# PARAMETRIK2L.net
KiCad netlist of a schematic drawn in EAGLE
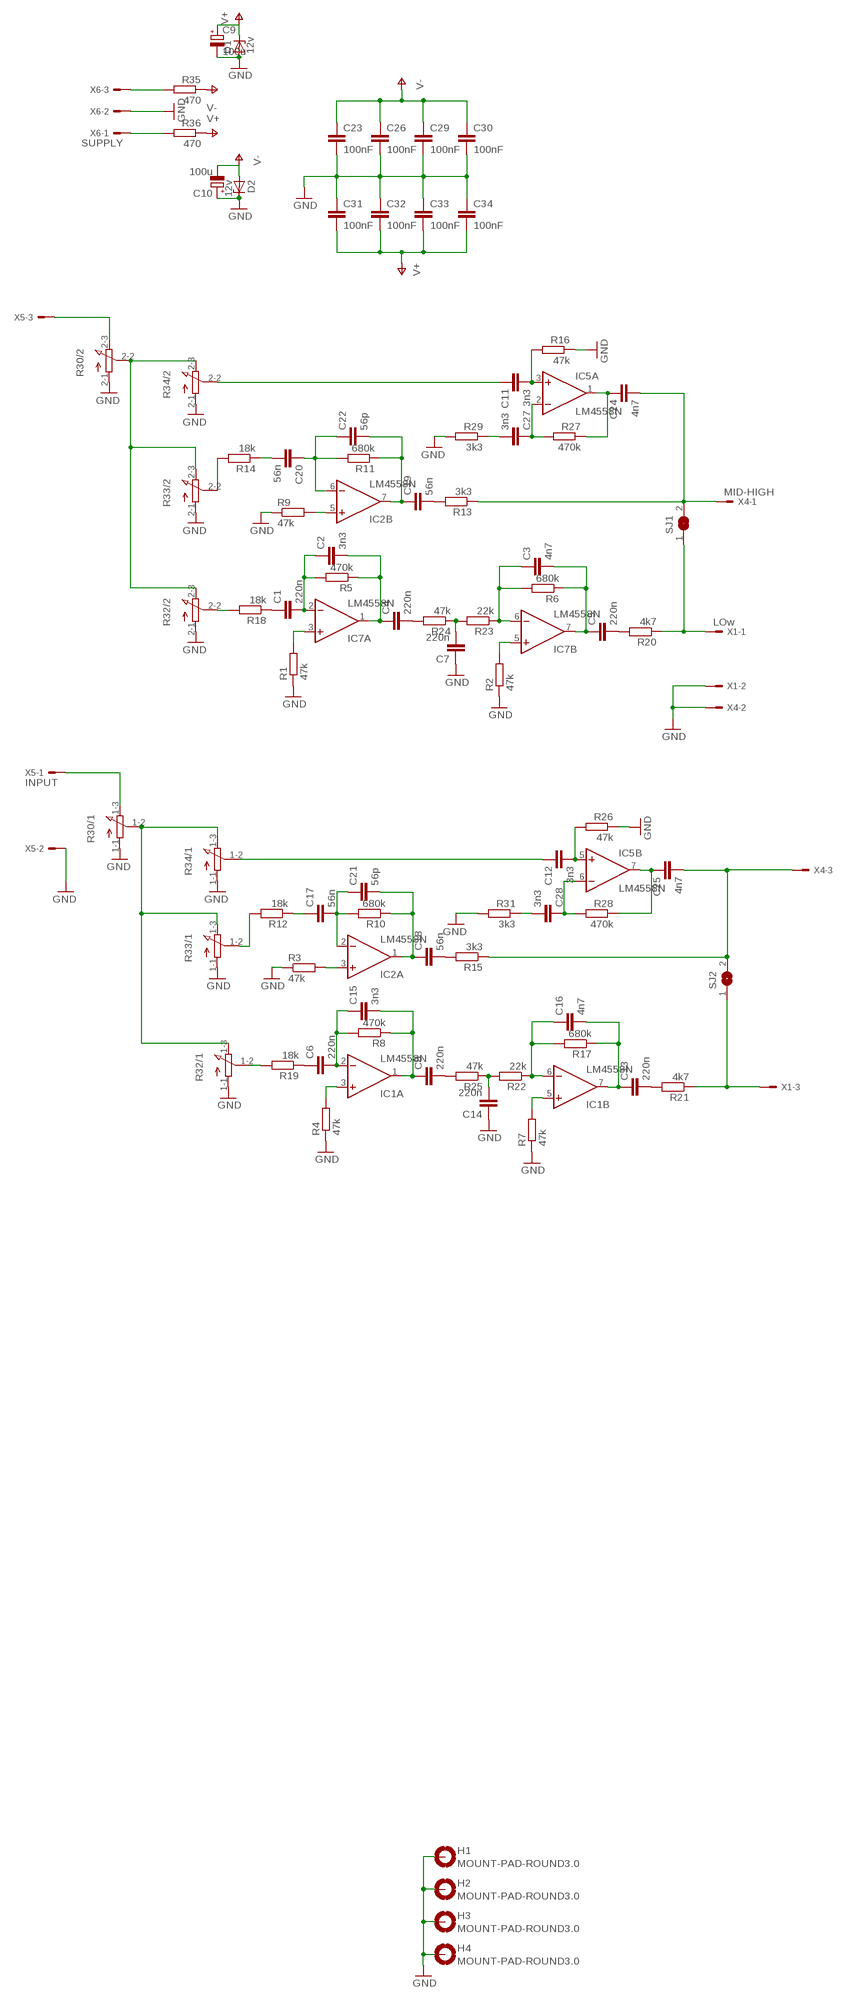
[diagram p0: schematic, sheet 1]

(export (version "E")
  (design (tool "Eeschema 10.0.6"))
  (components
    (comp (ref "C1")
      (value "220n")
      (footprint "eagle-import:C050-030X075")
      (libsource (lib "eagle-import") (part "C-EU050-030X075"))
    )
    (comp (ref "C2")
      (value "3n3")
      (footprint "eagle-import:C025-024X044")
      (libsource (lib "eagle-import") (part "C-EU025-024X044"))
    )
    (comp (ref "C3")
      (value "4n7")
      (footprint "eagle-import:C025-024X044")
      (libsource (lib "eagle-import") (part "C-EU025-024X044"))
    )
    (comp (ref "C4")
      (value "220n")
      (footprint "eagle-import:C050-030X075")
      (libsource (lib "eagle-import") (part "C-EU050-030X075"))
    )
    (comp (ref "C5")
      (value "220n")
      (footprint "eagle-import:C050-030X075")
      (libsource (lib "eagle-import") (part "C-EU050-030X075"))
    )
    (comp (ref "C6")
      (value "220n")
      (footprint "eagle-import:C050-030X075")
      (libsource (lib "eagle-import") (part "C-EU050-030X075"))
    )
    (comp (ref "C7")
      (value "220n")
      (footprint "eagle-import:C050-030X075")
      (libsource (lib "eagle-import") (part "C-EU050-030X075"))
    )
    (comp (ref "C8")
      (value "220n")
      (footprint "eagle-import:C050-030X075")
      (libsource (lib "eagle-import") (part "C-EU050-030X075"))
    )
    (comp (ref "C9")
      (value "100u")
      (footprint "eagle-import:E2,5-6")
      (libsource (lib "eagle-import") (part "CPOL-EUE2.5-6"))
    )
    (comp (ref "C10")
      (value "100u")
      (footprint "eagle-import:E2,5-6")
      (libsource (lib "eagle-import") (part "CPOL-EUE2.5-6"))
    )
    (comp (ref "C11")
      (value "3n3")
      (footprint "eagle-import:C025-024X044")
      (libsource (lib "eagle-import") (part "C-EU025-024X044"))
    )
    (comp (ref "C12")
      (value "3n3")
      (footprint "eagle-import:C025-024X044")
      (libsource (lib "eagle-import") (part "C-EU025-024X044"))
    )
    (comp (ref "C13")
      (value "220n")
      (footprint "eagle-import:C050-030X075")
      (libsource (lib "eagle-import") (part "C-EU050-030X075"))
    )
    (comp (ref "C14")
      (value "220n")
      (footprint "eagle-import:C050-030X075")
      (libsource (lib "eagle-import") (part "C-EU050-030X075"))
    )
    (comp (ref "C15")
      (value "3n3")
      (footprint "eagle-import:C025-024X044")
      (libsource (lib "eagle-import") (part "C-EU025-024X044"))
    )
    (comp (ref "C16")
      (value "4n7")
      (footprint "eagle-import:C025-024X044")
      (libsource (lib "eagle-import") (part "C-EU025-024X044"))
    )
    (comp (ref "C17")
      (value "56n")
      (footprint "eagle-import:C050-030X075")
      (libsource (lib "eagle-import") (part "C-EU050-030X075"))
    )
    (comp (ref "C18")
      (value "56n")
      (footprint "eagle-import:C050-030X075")
      (libsource (lib "eagle-import") (part "C-EU050-030X075"))
    )
    (comp (ref "C19")
      (value "56n")
      (footprint "eagle-import:C050-030X075")
      (libsource (lib "eagle-import") (part "C-EU050-030X075"))
    )
    (comp (ref "C20")
      (value "56n")
      (footprint "eagle-import:C050-030X075")
      (libsource (lib "eagle-import") (part "C-EU050-030X075"))
    )
    (comp (ref "C21")
      (value "56p")
      (footprint "eagle-import:C025-024X044")
      (libsource (lib "eagle-import") (part "C-EU025-024X044"))
    )
    (comp (ref "C22")
      (value "56p")
      (footprint "eagle-import:C025-024X044")
      (libsource (lib "eagle-import") (part "C-EU025-024X044"))
    )
    (comp (ref "C23")
      (value "100nF")
      (footprint "eagle-import:C050-024X044")
      (libsource (lib "eagle-import") (part "C-EU050-024X044"))
    )
    (comp (ref "C24")
      (value "4n7")
      (footprint "eagle-import:C025-024X044")
      (libsource (lib "eagle-import") (part "C-EU025-024X044"))
    )
    (comp (ref "C25")
      (value "4n7")
      (footprint "eagle-import:C025-024X044")
      (libsource (lib "eagle-import") (part "C-EU025-024X044"))
    )
    (comp (ref "C26")
      (value "100nF")
      (footprint "eagle-import:C050-024X044")
      (libsource (lib "eagle-import") (part "C-EU050-024X044"))
    )
    (comp (ref "C27")
      (value "3n3")
      (footprint "eagle-import:C025-024X044")
      (libsource (lib "eagle-import") (part "C-EU025-024X044"))
    )
    (comp (ref "C28")
      (value "3n3")
      (footprint "eagle-import:C025-024X044")
      (libsource (lib "eagle-import") (part "C-EU025-024X044"))
    )
    (comp (ref "C29")
      (value "100nF")
      (footprint "eagle-import:C050-024X044")
      (libsource (lib "eagle-import") (part "C-EU050-024X044"))
    )
    (comp (ref "C30")
      (value "100nF")
      (footprint "eagle-import:C050-024X044")
      (libsource (lib "eagle-import") (part "C-EU050-024X044"))
    )
    (comp (ref "C31")
      (value "100nF")
      (footprint "eagle-import:C050-024X044")
      (libsource (lib "eagle-import") (part "C-EU050-024X044"))
    )
    (comp (ref "C32")
      (value "100nF")
      (footprint "eagle-import:C050-024X044")
      (libsource (lib "eagle-import") (part "C-EU050-024X044"))
    )
    (comp (ref "C33")
      (value "100nF")
      (footprint "eagle-import:C050-024X044")
      (libsource (lib "eagle-import") (part "C-EU050-024X044"))
    )
    (comp (ref "C34")
      (value "100nF")
      (footprint "eagle-import:C050-024X044")
      (libsource (lib "eagle-import") (part "C-EU050-024X044"))
    )
    (comp (ref "D1")
      (value "12v")
      (footprint "eagle-import:DO35Z10")
      (libsource (lib "eagle-import") (part "1N821"))
    )
    (comp (ref "D2")
      (value "12v")
      (footprint "eagle-import:DO35Z10")
      (libsource (lib "eagle-import") (part "1N821"))
    )
    (comp (ref "H1")
      (value "MOUNT-PAD-ROUND3.0")
      (footprint "eagle-import:3,0-PAD")
      (libsource (lib "eagle-import") (part "MOUNT-PAD-ROUND3.0"))
    )
    (comp (ref "H2")
      (value "MOUNT-PAD-ROUND3.0")
      (footprint "eagle-import:3,0-PAD")
      (libsource (lib "eagle-import") (part "MOUNT-PAD-ROUND3.0"))
    )
    (comp (ref "H3")
      (value "MOUNT-PAD-ROUND3.0")
      (footprint "eagle-import:3,0-PAD")
      (libsource (lib "eagle-import") (part "MOUNT-PAD-ROUND3.0"))
    )
    (comp (ref "H4")
      (value "MOUNT-PAD-ROUND3.0")
      (footprint "eagle-import:3,0-PAD")
      (libsource (lib "eagle-import") (part "MOUNT-PAD-ROUND3.0"))
    )
    (comp (ref "IC1")
      (value "LM4558N")
      (footprint "eagle-import:DIL08")
      (libsource (lib "eagle-import") (part "4558NLM"))
    )
    (comp (ref "IC2")
      (value "LM4558N")
      (footprint "eagle-import:DIL08")
      (libsource (lib "eagle-import") (part "4558NLM"))
    )
    (comp (ref "IC5")
      (value "LM4558N")
      (footprint "eagle-import:DIL08")
      (libsource (lib "eagle-import") (part "4558NLM"))
    )
    (comp (ref "IC7")
      (value "LM4558N")
      (footprint "eagle-import:DIL08")
      (libsource (lib "eagle-import") (part "4558NLM"))
    )
    (comp (ref "R1")
      (value "47k")
      (footprint "eagle-import:0207_2V")
      (libsource (lib "eagle-import") (part "R-EU_0207/2V"))
    )
    (comp (ref "R2")
      (value "47k")
      (footprint "eagle-import:0207_2V")
      (libsource (lib "eagle-import") (part "R-EU_0207/2V"))
    )
    (comp (ref "R3")
      (value "47k")
      (footprint "eagle-import:0207_2V")
      (libsource (lib "eagle-import") (part "R-EU_0207/2V"))
    )
    (comp (ref "R4")
      (value "47k")
      (footprint "eagle-import:0207_2V")
      (libsource (lib "eagle-import") (part "R-EU_0207/2V"))
    )
    (comp (ref "R5")
      (value "470k")
      (footprint "eagle-import:0207_2V")
      (libsource (lib "eagle-import") (part "R-EU_0207/2V"))
    )
    (comp (ref "R6")
      (value "680k")
      (footprint "eagle-import:0207_2V")
      (libsource (lib "eagle-import") (part "R-EU_0207/2V"))
    )
    (comp (ref "R7")
      (value "47k")
      (footprint "eagle-import:0207_2V")
      (libsource (lib "eagle-import") (part "R-EU_0207/2V"))
    )
    (comp (ref "R8")
      (value "470k")
      (footprint "eagle-import:0207_2V")
      (libsource (lib "eagle-import") (part "R-EU_0207/2V"))
    )
    (comp (ref "R9")
      (value "47k")
      (footprint "eagle-import:0207_2V")
      (libsource (lib "eagle-import") (part "R-EU_0207/2V"))
    )
    (comp (ref "R10")
      (value "680k")
      (footprint "eagle-import:0207_2V")
      (libsource (lib "eagle-import") (part "R-EU_0207/2V"))
    )
    (comp (ref "R11")
      (value "680k")
      (footprint "eagle-import:0207_2V")
      (libsource (lib "eagle-import") (part "R-EU_0207/2V"))
    )
    (comp (ref "R12")
      (value "18k")
      (footprint "eagle-import:0207_2V")
      (libsource (lib "eagle-import") (part "R-EU_0207/2V"))
    )
    (comp (ref "R13")
      (value "3k3")
      (footprint "eagle-import:0207_2V")
      (libsource (lib "eagle-import") (part "R-EU_0207/2V"))
    )
    (comp (ref "R14")
      (value "18k")
      (footprint "eagle-import:0207_2V")
      (libsource (lib "eagle-import") (part "R-EU_0207/2V"))
    )
    (comp (ref "R15")
      (value "3k3")
      (footprint "eagle-import:0207_2V")
      (libsource (lib "eagle-import") (part "R-EU_0207/2V"))
    )
    (comp (ref "R16")
      (value "47k")
      (footprint "eagle-import:0207_2V")
      (libsource (lib "eagle-import") (part "R-EU_0207/2V"))
    )
    (comp (ref "R17")
      (value "680k")
      (footprint "eagle-import:0207_2V")
      (libsource (lib "eagle-import") (part "R-EU_0207/2V"))
    )
    (comp (ref "R18")
      (value "18k")
      (footprint "eagle-import:0207_2V")
      (libsource (lib "eagle-import") (part "R-EU_0207/2V"))
    )
    (comp (ref "R19")
      (value "18k")
      (footprint "eagle-import:0207_2V")
      (libsource (lib "eagle-import") (part "R-EU_0207/2V"))
    )
    (comp (ref "R20")
      (value "4k7")
      (footprint "eagle-import:0207_2V")
      (libsource (lib "eagle-import") (part "R-EU_0207/2V"))
    )
    (comp (ref "R21")
      (value "4k7")
      (footprint "eagle-import:0207_2V")
      (libsource (lib "eagle-import") (part "R-EU_0207/2V"))
    )
    (comp (ref "R22")
      (value "22k")
      (footprint "eagle-import:0207_2V")
      (libsource (lib "eagle-import") (part "R-EU_0207/2V"))
    )
    (comp (ref "R23")
      (value "22k")
      (footprint "eagle-import:0207_2V")
      (libsource (lib "eagle-import") (part "R-EU_0207/2V"))
    )
    (comp (ref "R24")
      (value "47k")
      (footprint "eagle-import:0207_2V")
      (libsource (lib "eagle-import") (part "R-EU_0207/2V"))
    )
    (comp (ref "R25")
      (value "47k")
      (footprint "eagle-import:0207_2V")
      (libsource (lib "eagle-import") (part "R-EU_0207/2V"))
    )
    (comp (ref "R26")
      (value "47k")
      (footprint "eagle-import:0207_2V")
      (libsource (lib "eagle-import") (part "R-EU_0207/2V"))
    )
    (comp (ref "R27")
      (value "470k")
      (footprint "eagle-import:0207_2V")
      (libsource (lib "eagle-import") (part "R-EU_0207/2V"))
    )
    (comp (ref "R28")
      (value "470k")
      (footprint "eagle-import:0207_2V")
      (libsource (lib "eagle-import") (part "R-EU_0207/2V"))
    )
    (comp (ref "R29")
      (value "3k3")
      (footprint "eagle-import:0207_2V")
      (libsource (lib "eagle-import") (part "R-EU_0207/2V"))
    )
    (comp (ref "R30")
      (value "3RP/1610G")
      (footprint "eagle-import:3RP_1610G")
      (libsource (lib "eagle-import") (part "3RP/1610G"))
    )
    (comp (ref "R31")
      (value "3k3")
      (footprint "eagle-import:0207_2V")
      (libsource (lib "eagle-import") (part "R-EU_0207/2V"))
    )
    (comp (ref "R32")
      (value "3RP/1610G")
      (footprint "eagle-import:3RP_1610G")
      (libsource (lib "eagle-import") (part "3RP/1610G"))
    )
    (comp (ref "R33")
      (value "3RP/1610G")
      (footprint "eagle-import:3RP_1610G")
      (libsource (lib "eagle-import") (part "3RP/1610G"))
    )
    (comp (ref "R34")
      (value "3RP/1610G")
      (footprint "eagle-import:3RP_1610G")
      (libsource (lib "eagle-import") (part "3RP/1610G"))
    )
    (comp (ref "R35")
      (value "470")
      (footprint "eagle-import:0207_10")
      (libsource (lib "eagle-import") (part "R-EU_0207/10"))
    )
    (comp (ref "R36")
      (value "470")
      (footprint "eagle-import:0207_10")
      (libsource (lib "eagle-import") (part "R-EU_0207/10"))
    )
    (comp (ref "SJ1") (value "SJ") (footprint "eagle-import:SJ") (libsource (lib "eagle-import") (part "SJ")))
    (comp (ref "SJ2") (value "SJ") (footprint "eagle-import:SJ") (libsource (lib "eagle-import") (part "SJ")))
    (comp (ref "X1")
      (value "LOw")
      (footprint "eagle-import:22-23-2031")
      (fields (field (name "MF") "MOLEX") (field (name "MPN") "22-23-2031"))
      (libsource (lib "eagle-import") (part "22-23-2031"))
    )
    (comp (ref "X4")
      (value "MID-HIGH")
      (footprint "eagle-import:22-23-2031")
      (fields (field (name "MF") "MOLEX") (field (name "MPN") "22-23-2031"))
      (libsource (lib "eagle-import") (part "22-23-2031"))
    )
    (comp (ref "X5")
      (value "INPUT")
      (footprint "eagle-import:22-23-2031")
      (fields (field (name "MF") "MOLEX") (field (name "MPN") "22-23-2031"))
      (libsource (lib "eagle-import") (part "22-23-2031"))
    )
    (comp (ref "X6")
      (value "SUPPLY")
      (footprint "eagle-import:22-23-2031")
      (fields (field (name "MF") "MOLEX") (field (name "MPN") "22-23-2031"))
      (libsource (lib "eagle-import") (part "22-23-2031"))
    )
  )
  (nets
    (net (code "1") (name "GND") (class "Default")
      (node (ref "C10") (pin "+") (pinfunction "+_+") (pintype "passive"))
      (node (ref "C14") (pin "1") (pinfunction "1_1") (pintype "passive"))
      (node (ref "C23") (pin "2") (pinfunction "2_2") (pintype "passive"))
      (node (ref "C26") (pin "2") (pinfunction "2_2") (pintype "passive"))
      (node (ref "C29") (pin "2") (pinfunction "2_2") (pintype "passive"))
      (node (ref "C30") (pin "2") (pinfunction "2_2") (pintype "passive"))
      (node (ref "C31") (pin "1") (pinfunction "1_1") (pintype "passive"))
      (node (ref "C32") (pin "1") (pinfunction "1_1") (pintype "passive"))
      (node (ref "C33") (pin "1") (pinfunction "1_1") (pintype "passive"))
      (node (ref "C34") (pin "1") (pinfunction "1_1") (pintype "passive"))
      (node (ref "C7") (pin "1") (pinfunction "1_1") (pintype "passive"))
      (node (ref "C9") (pin "-") (pinfunction "-_-") (pintype "passive"))
      (node (ref "D1") (pin "A") (pinfunction "A_A") (pintype "passive"))
      (node (ref "D2") (pin "C") (pinfunction "C_C") (pintype "passive"))
      (node (ref "H1") (pin "B3,0") (pinfunction "MOUNT_B3,0") (pintype "passive"))
      (node (ref "H2") (pin "B3,0") (pinfunction "MOUNT_B3,0") (pintype "passive"))
      (node (ref "H3") (pin "B3,0") (pinfunction "MOUNT_B3,0") (pintype "passive"))
      (node (ref "H4") (pin "B3,0") (pinfunction "MOUNT_B3,0") (pintype "passive"))
      (node (ref "R1") (pin "1") (pinfunction "1_1") (pintype "passive"))
      (node (ref "R16") (pin "1") (pinfunction "1_1") (pintype "passive"))
      (node (ref "R2") (pin "1") (pinfunction "1_1") (pintype "passive"))
      (node (ref "R26") (pin "1") (pinfunction "1_1") (pintype "passive"))
      (node (ref "R29") (pin "2") (pinfunction "2_2") (pintype "passive"))
      (node (ref "R3") (pin "1") (pinfunction "1_1") (pintype "passive"))
      (node (ref "R30") (pin "1-1") (pinfunction "A_1-1") (pintype "passive"))
      (node (ref "R30") (pin "2-1") (pinfunction "A_2-1") (pintype "passive"))
      (node (ref "R31") (pin "2") (pinfunction "2_2") (pintype "passive"))
      (node (ref "R32") (pin "1-1") (pinfunction "A_1-1") (pintype "passive"))
      (node (ref "R32") (pin "2-1") (pinfunction "A_2-1") (pintype "passive"))
      (node (ref "R33") (pin "1-1") (pinfunction "A_1-1") (pintype "passive"))
      (node (ref "R33") (pin "2-1") (pinfunction "A_2-1") (pintype "passive"))
      (node (ref "R34") (pin "1-1") (pinfunction "A_1-1") (pintype "passive"))
      (node (ref "R34") (pin "2-1") (pinfunction "A_2-1") (pintype "passive"))
      (node (ref "R4") (pin "1") (pinfunction "1_1") (pintype "passive"))
      (node (ref "R7") (pin "1") (pinfunction "1_1") (pintype "passive"))
      (node (ref "R9") (pin "1") (pinfunction "1_1") (pintype "passive"))
      (node (ref "X1") (pin "2") (pinfunction "S_2") (pintype "passive"))
      (node (ref "X4") (pin "2") (pinfunction "S_2") (pintype "passive"))
      (node (ref "X5") (pin "2") (pinfunction "S_2") (pintype "passive"))
      (node (ref "X6") (pin "2") (pinfunction "S_2") (pintype "passive"))
    )
    (net (code "2") (name "Net-(C1-Pad1)") (class "Default")
      (node (ref "C1") (pin "1") (pinfunction "1_1") (pintype "passive"))
      (node (ref "R18") (pin "1") (pinfunction "1_1") (pintype "passive"))
    )
    (net (code "3") (name "Net-(C4-Pad2)") (class "Default")
      (node (ref "C4") (pin "2") (pinfunction "2_2") (pintype "passive"))
      (node (ref "R24") (pin "2") (pinfunction "2_2") (pintype "passive"))
    )
    (net (code "4") (name "Net-(C5-Pad2)") (class "Default")
      (node (ref "C5") (pin "2") (pinfunction "2_2") (pintype "passive"))
      (node (ref "R20") (pin "2") (pinfunction "2_2") (pintype "passive"))
    )
    (net (code "5") (name "Net-(C6-Pad1)") (class "Default")
      (node (ref "C6") (pin "1") (pinfunction "1_1") (pintype "passive"))
      (node (ref "R19") (pin "1") (pinfunction "1_1") (pintype "passive"))
    )
    (net (code "6") (name "Net-(C7-Pad2)") (class "Default")
      (node (ref "C7") (pin "2") (pinfunction "2_2") (pintype "passive"))
      (node (ref "R23") (pin "2") (pinfunction "2_2") (pintype "passive"))
      (node (ref "R24") (pin "1") (pinfunction "1_1") (pintype "passive"))
    )
    (net (code "7") (name "Net-(C8-Pad2)") (class "Default")
      (node (ref "C8") (pin "2") (pinfunction "2_2") (pintype "passive"))
      (node (ref "R25") (pin "2") (pinfunction "2_2") (pintype "passive"))
    )
    (net (code "8") (name "Net-(C13-Pad2)") (class "Default")
      (node (ref "C13") (pin "2") (pinfunction "2_2") (pintype "passive"))
      (node (ref "R21") (pin "2") (pinfunction "2_2") (pintype "passive"))
    )
    (net (code "9") (name "Net-(C14-Pad2)") (class "Default")
      (node (ref "C14") (pin "2") (pinfunction "2_2") (pintype "passive"))
      (node (ref "R22") (pin "2") (pinfunction "2_2") (pintype "passive"))
      (node (ref "R25") (pin "1") (pinfunction "1_1") (pintype "passive"))
    )
    (net (code "10") (name "Net-(C17-Pad1)") (class "Default")
      (node (ref "C17") (pin "1") (pinfunction "1_1") (pintype "passive"))
      (node (ref "R12") (pin "1") (pinfunction "1_1") (pintype "passive"))
    )
    (net (code "11") (name "Net-(C18-Pad2)") (class "Default")
      (node (ref "C18") (pin "2") (pinfunction "2_2") (pintype "passive"))
      (node (ref "R15") (pin "2") (pinfunction "2_2") (pintype "passive"))
    )
    (net (code "12") (name "Net-(C19-Pad2)") (class "Default")
      (node (ref "C19") (pin "2") (pinfunction "2_2") (pintype "passive"))
      (node (ref "R13") (pin "2") (pinfunction "2_2") (pintype "passive"))
    )
    (net (code "13") (name "Net-(C20-Pad2)") (class "Default")
      (node (ref "C20") (pin "2") (pinfunction "2_2") (pintype "passive"))
      (node (ref "R14") (pin "1") (pinfunction "1_1") (pintype "passive"))
    )
    (net (code "14") (name "Net-(C27-Pad2)") (class "Default")
      (node (ref "C27") (pin "2") (pinfunction "2_2") (pintype "passive"))
      (node (ref "R29") (pin "1") (pinfunction "1_1") (pintype "passive"))
    )
    (net (code "15") (name "Net-(C28-Pad2)") (class "Default")
      (node (ref "C28") (pin "2") (pinfunction "2_2") (pintype "passive"))
      (node (ref "R31") (pin "1") (pinfunction "1_1") (pintype "passive"))
    )
    (net (code "16") (name "Net-(IC1A-+IN)") (class "Default")
      (node (ref "IC1") (pin "3") (pinfunction "+IN_3") (pintype "input"))
      (node (ref "R4") (pin "2") (pinfunction "2_2") (pintype "passive"))
    )
    (net (code "17") (name "Net-(IC1A--IN)") (class "Default")
      (node (ref "C15") (pin "1") (pinfunction "1_1") (pintype "passive"))
      (node (ref "C6") (pin "2") (pinfunction "2_2") (pintype "passive"))
      (node (ref "IC1") (pin "2") (pinfunction "-IN_2") (pintype "input"))
      (node (ref "R8") (pin "2") (pinfunction "2_2") (pintype "passive"))
    )
    (net (code "18") (name "Net-(IC1A-OUT)") (class "Default")
      (node (ref "C15") (pin "2") (pinfunction "2_2") (pintype "passive"))
      (node (ref "C8") (pin "1") (pinfunction "1_1") (pintype "passive"))
      (node (ref "IC1") (pin "1") (pinfunction "OUT_1") (pintype "output"))
      (node (ref "R8") (pin "1") (pinfunction "1_1") (pintype "passive"))
    )
    (net (code "19") (name "Net-(IC1B-+IN)") (class "Default")
      (node (ref "IC1") (pin "5") (pinfunction "+IN_5") (pintype "input"))
      (node (ref "R7") (pin "2") (pinfunction "2_2") (pintype "passive"))
    )
    (net (code "20") (name "Net-(IC1B--IN)") (class "Default")
      (node (ref "C16") (pin "1") (pinfunction "1_1") (pintype "passive"))
      (node (ref "IC1") (pin "6") (pinfunction "-IN_6") (pintype "input"))
      (node (ref "R17") (pin "2") (pinfunction "2_2") (pintype "passive"))
      (node (ref "R22") (pin "1") (pinfunction "1_1") (pintype "passive"))
    )
    (net (code "21") (name "Net-(IC1B-OUT)") (class "Default")
      (node (ref "C13") (pin "1") (pinfunction "1_1") (pintype "passive"))
      (node (ref "C16") (pin "2") (pinfunction "2_2") (pintype "passive"))
      (node (ref "IC1") (pin "7") (pinfunction "OUT_7") (pintype "output"))
      (node (ref "R17") (pin "1") (pinfunction "1_1") (pintype "passive"))
    )
    (net (code "22") (name "Net-(IC2A-+IN)") (class "Default")
      (node (ref "IC2") (pin "3") (pinfunction "+IN_3") (pintype "input"))
      (node (ref "R3") (pin "2") (pinfunction "2_2") (pintype "passive"))
    )
    (net (code "23") (name "Net-(IC2A--IN)") (class "Default")
      (node (ref "C17") (pin "2") (pinfunction "2_2") (pintype "passive"))
      (node (ref "C21") (pin "1") (pinfunction "1_1") (pintype "passive"))
      (node (ref "IC2") (pin "2") (pinfunction "-IN_2") (pintype "input"))
      (node (ref "R10") (pin "2") (pinfunction "2_2") (pintype "passive"))
    )
    (net (code "24") (name "Net-(IC2A-OUT)") (class "Default")
      (node (ref "C18") (pin "1") (pinfunction "1_1") (pintype "passive"))
      (node (ref "C21") (pin "2") (pinfunction "2_2") (pintype "passive"))
      (node (ref "IC2") (pin "1") (pinfunction "OUT_1") (pintype "output"))
      (node (ref "R10") (pin "1") (pinfunction "1_1") (pintype "passive"))
    )
    (net (code "25") (name "Net-(IC2B-+IN)") (class "Default")
      (node (ref "IC2") (pin "5") (pinfunction "+IN_5") (pintype "input"))
      (node (ref "R9") (pin "2") (pinfunction "2_2") (pintype "passive"))
    )
    (net (code "26") (name "Net-(IC2B--IN)") (class "Default")
      (node (ref "C20") (pin "1") (pinfunction "1_1") (pintype "passive"))
      (node (ref "C22") (pin "1") (pinfunction "1_1") (pintype "passive"))
      (node (ref "IC2") (pin "6") (pinfunction "-IN_6") (pintype "input"))
      (node (ref "R11") (pin "2") (pinfunction "2_2") (pintype "passive"))
    )
    (net (code "27") (name "Net-(IC2B-OUT)") (class "Default")
      (node (ref "C19") (pin "1") (pinfunction "1_1") (pintype "passive"))
      (node (ref "C22") (pin "2") (pinfunction "2_2") (pintype "passive"))
      (node (ref "IC2") (pin "7") (pinfunction "OUT_7") (pintype "output"))
      (node (ref "R11") (pin "1") (pinfunction "1_1") (pintype "passive"))
    )
    (net (code "28") (name "Net-(IC5A-+IN)") (class "Default")
      (node (ref "C11") (pin "2") (pinfunction "2_2") (pintype "passive"))
      (node (ref "IC5") (pin "3") (pinfunction "+IN_3") (pintype "input"))
      (node (ref "R16") (pin "2") (pinfunction "2_2") (pintype "passive"))
    )
    (net (code "29") (name "Net-(IC5A--IN)") (class "Default")
      (node (ref "C27") (pin "1") (pinfunction "1_1") (pintype "passive"))
      (node (ref "IC5") (pin "2") (pinfunction "-IN_2") (pintype "input"))
      (node (ref "R27") (pin "2") (pinfunction "2_2") (pintype "passive"))
    )
    (net (code "30") (name "Net-(IC5A-OUT)") (class "Default")
      (node (ref "C24") (pin "1") (pinfunction "1_1") (pintype "passive"))
      (node (ref "IC5") (pin "1") (pinfunction "OUT_1") (pintype "output"))
      (node (ref "R27") (pin "1") (pinfunction "1_1") (pintype "passive"))
    )
    (net (code "31") (name "Net-(IC5B-+IN)") (class "Default")
      (node (ref "C12") (pin "2") (pinfunction "2_2") (pintype "passive"))
      (node (ref "IC5") (pin "5") (pinfunction "+IN_5") (pintype "input"))
      (node (ref "R26") (pin "2") (pinfunction "2_2") (pintype "passive"))
    )
    (net (code "32") (name "Net-(IC5B--IN)") (class "Default")
      (node (ref "C28") (pin "1") (pinfunction "1_1") (pintype "passive"))
      (node (ref "IC5") (pin "6") (pinfunction "-IN_6") (pintype "input"))
      (node (ref "R28") (pin "2") (pinfunction "2_2") (pintype "passive"))
    )
    (net (code "33") (name "Net-(IC5B-OUT)") (class "Default")
      (node (ref "C25") (pin "1") (pinfunction "1_1") (pintype "passive"))
      (node (ref "IC5") (pin "7") (pinfunction "OUT_7") (pintype "output"))
      (node (ref "R28") (pin "1") (pinfunction "1_1") (pintype "passive"))
    )
    (net (code "34") (name "Net-(IC7A-+IN)") (class "Default")
      (node (ref "IC7") (pin "3") (pinfunction "+IN_3") (pintype "input"))
      (node (ref "R1") (pin "2") (pinfunction "2_2") (pintype "passive"))
    )
    (net (code "35") (name "Net-(IC7A--IN)") (class "Default")
      (node (ref "C1") (pin "2") (pinfunction "2_2") (pintype "passive"))
      (node (ref "C2") (pin "1") (pinfunction "1_1") (pintype "passive"))
      (node (ref "IC7") (pin "2") (pinfunction "-IN_2") (pintype "input"))
      (node (ref "R5") (pin "2") (pinfunction "2_2") (pintype "passive"))
    )
    (net (code "36") (name "Net-(IC7A-OUT)") (class "Default")
      (node (ref "C2") (pin "2") (pinfunction "2_2") (pintype "passive"))
      (node (ref "C4") (pin "1") (pinfunction "1_1") (pintype "passive"))
      (node (ref "IC7") (pin "1") (pinfunction "OUT_1") (pintype "output"))
      (node (ref "R5") (pin "1") (pinfunction "1_1") (pintype "passive"))
    )
    (net (code "37") (name "Net-(IC7B-+IN)") (class "Default")
      (node (ref "IC7") (pin "5") (pinfunction "+IN_5") (pintype "input"))
      (node (ref "R2") (pin "2") (pinfunction "2_2") (pintype "passive"))
    )
    (net (code "38") (name "Net-(IC7B--IN)") (class "Default")
      (node (ref "C3") (pin "1") (pinfunction "1_1") (pintype "passive"))
      (node (ref "IC7") (pin "6") (pinfunction "-IN_6") (pintype "input"))
      (node (ref "R23") (pin "1") (pinfunction "1_1") (pintype "passive"))
      (node (ref "R6") (pin "2") (pinfunction "2_2") (pintype "passive"))
    )
    (net (code "39") (name "Net-(IC7B-OUT)") (class "Default")
      (node (ref "C3") (pin "2") (pinfunction "2_2") (pintype "passive"))
      (node (ref "C5") (pin "1") (pinfunction "1_1") (pintype "passive"))
      (node (ref "IC7") (pin "7") (pinfunction "OUT_7") (pintype "output"))
      (node (ref "R6") (pin "1") (pinfunction "1_1") (pintype "passive"))
    )
    (net (code "40") (name "Net-(R30A-E)") (class "Default")
      (node (ref "R30") (pin "1-3") (pinfunction "E_1-3") (pintype "passive"))
      (node (ref "X5") (pin "1") (pinfunction "S_1") (pintype "passive"))
    )
    (net (code "41") (name "Net-(R30A-S)") (class "Default")
      (node (ref "R30") (pin "1-2") (pinfunction "S_1-2") (pintype "passive"))
      (node (ref "R32") (pin "1-3") (pinfunction "E_1-3") (pintype "passive"))
      (node (ref "R33") (pin "1-3") (pinfunction "E_1-3") (pintype "passive"))
      (node (ref "R34") (pin "1-3") (pinfunction "E_1-3") (pintype "passive"))
    )
    (net (code "42") (name "Net-(R30B-E)") (class "Default")
      (node (ref "R30") (pin "2-3") (pinfunction "E_2-3") (pintype "passive"))
      (node (ref "X5") (pin "3") (pinfunction "S_3") (pintype "passive"))
    )
    (net (code "43") (name "Net-(R30B-S)") (class "Default")
      (node (ref "R30") (pin "2-2") (pinfunction "S_2-2") (pintype "passive"))
      (node (ref "R32") (pin "2-3") (pinfunction "E_2-3") (pintype "passive"))
      (node (ref "R33") (pin "2-3") (pinfunction "E_2-3") (pintype "passive"))
      (node (ref "R34") (pin "2-3") (pinfunction "E_2-3") (pintype "passive"))
    )
    (net (code "44") (name "Net-(R32A-S)") (class "Default")
      (node (ref "R19") (pin "2") (pinfunction "2_2") (pintype "passive"))
      (node (ref "R32") (pin "1-2") (pinfunction "S_1-2") (pintype "passive"))
    )
    (net (code "45") (name "Net-(R32B-S)") (class "Default")
      (node (ref "R18") (pin "2") (pinfunction "2_2") (pintype "passive"))
      (node (ref "R32") (pin "2-2") (pinfunction "S_2-2") (pintype "passive"))
    )
    (net (code "46") (name "Net-(R33A-S)") (class "Default")
      (node (ref "R12") (pin "2") (pinfunction "2_2") (pintype "passive"))
      (node (ref "R33") (pin "1-2") (pinfunction "S_1-2") (pintype "passive"))
    )
    (net (code "47") (name "Net-(R33B-S)") (class "Default")
      (node (ref "R14") (pin "2") (pinfunction "2_2") (pintype "passive"))
      (node (ref "R33") (pin "2-2") (pinfunction "S_2-2") (pintype "passive"))
    )
    (net (code "48") (name "Net-(R34A-S)") (class "Default")
      (node (ref "C12") (pin "1") (pinfunction "1_1") (pintype "passive"))
      (node (ref "R34") (pin "1-2") (pinfunction "S_1-2") (pintype "passive"))
    )
    (net (code "49") (name "Net-(R34B-S)") (class "Default")
      (node (ref "C11") (pin "1") (pinfunction "1_1") (pintype "passive"))
      (node (ref "R34") (pin "2-2") (pinfunction "S_2-2") (pintype "passive"))
    )
    (net (code "50") (name "Net-(X1A-S)") (class "Default")
      (node (ref "R20") (pin "1") (pinfunction "1_1") (pintype "passive"))
      (node (ref "SJ1") (pin "1") (pinfunction "1_1") (pintype "passive"))
      (node (ref "X1") (pin "1") (pinfunction "S_1") (pintype "passive"))
    )
    (net (code "51") (name "Net-(X1C-S)") (class "Default")
      (node (ref "R21") (pin "1") (pinfunction "1_1") (pintype "passive"))
      (node (ref "SJ2") (pin "1") (pinfunction "1_1") (pintype "passive"))
      (node (ref "X1") (pin "3") (pinfunction "S_3") (pintype "passive"))
    )
    (net (code "52") (name "Net-(X4A-S)") (class "Default")
      (node (ref "C24") (pin "2") (pinfunction "2_2") (pintype "passive"))
      (node (ref "R13") (pin "1") (pinfunction "1_1") (pintype "passive"))
      (node (ref "SJ1") (pin "2") (pinfunction "2_2") (pintype "passive"))
      (node (ref "X4") (pin "1") (pinfunction "S_1") (pintype "passive"))
    )
    (net (code "53") (name "Net-(X4C-S)") (class "Default")
      (node (ref "C25") (pin "2") (pinfunction "2_2") (pintype "passive"))
      (node (ref "R15") (pin "1") (pinfunction "1_1") (pintype "passive"))
      (node (ref "SJ2") (pin "2") (pinfunction "2_2") (pintype "passive"))
      (node (ref "X4") (pin "3") (pinfunction "S_3") (pintype "passive"))
    )
    (net (code "54") (name "Net-(X6A-S)") (class "Default")
      (node (ref "R36") (pin "2") (pinfunction "2_2") (pintype "passive"))
      (node (ref "X6") (pin "1") (pinfunction "S_1") (pintype "passive"))
    )
    (net (code "55") (name "Net-(X6C-S)") (class "Default")
      (node (ref "R35") (pin "2") (pinfunction "2_2") (pintype "passive"))
      (node (ref "X6") (pin "3") (pinfunction "S_3") (pintype "passive"))
    )
    (net (code "56") (name "V+") (class "Default")
      (node (ref "C31") (pin "2") (pinfunction "2_2") (pintype "passive"))
      (node (ref "C32") (pin "2") (pinfunction "2_2") (pintype "passive"))
      (node (ref "C33") (pin "2") (pinfunction "2_2") (pintype "passive"))
      (node (ref "C34") (pin "2") (pinfunction "2_2") (pintype "passive"))
      (node (ref "C9") (pin "+") (pinfunction "+_+") (pintype "passive"))
      (node (ref "D1") (pin "C") (pinfunction "C_C") (pintype "passive"))
      (node (ref "R36") (pin "1") (pinfunction "1_1") (pintype "passive"))
    )
    (net (code "57") (name "V-") (class "Default")
      (node (ref "C10") (pin "-") (pinfunction "-_-") (pintype "passive"))
      (node (ref "C23") (pin "1") (pinfunction "1_1") (pintype "passive"))
      (node (ref "C26") (pin "1") (pinfunction "1_1") (pintype "passive"))
      (node (ref "C29") (pin "1") (pinfunction "1_1") (pintype "passive"))
      (node (ref "C30") (pin "1") (pinfunction "1_1") (pintype "passive"))
      (node (ref "D2") (pin "A") (pinfunction "A_A") (pintype "passive"))
      (node (ref "R35") (pin "1") (pinfunction "1_1") (pintype "passive"))
    )
  )
)
